# ProPrj_51boardtest_2024-12-12.net
KiCad netlist of a schematic drawn in EasyEDA Pro
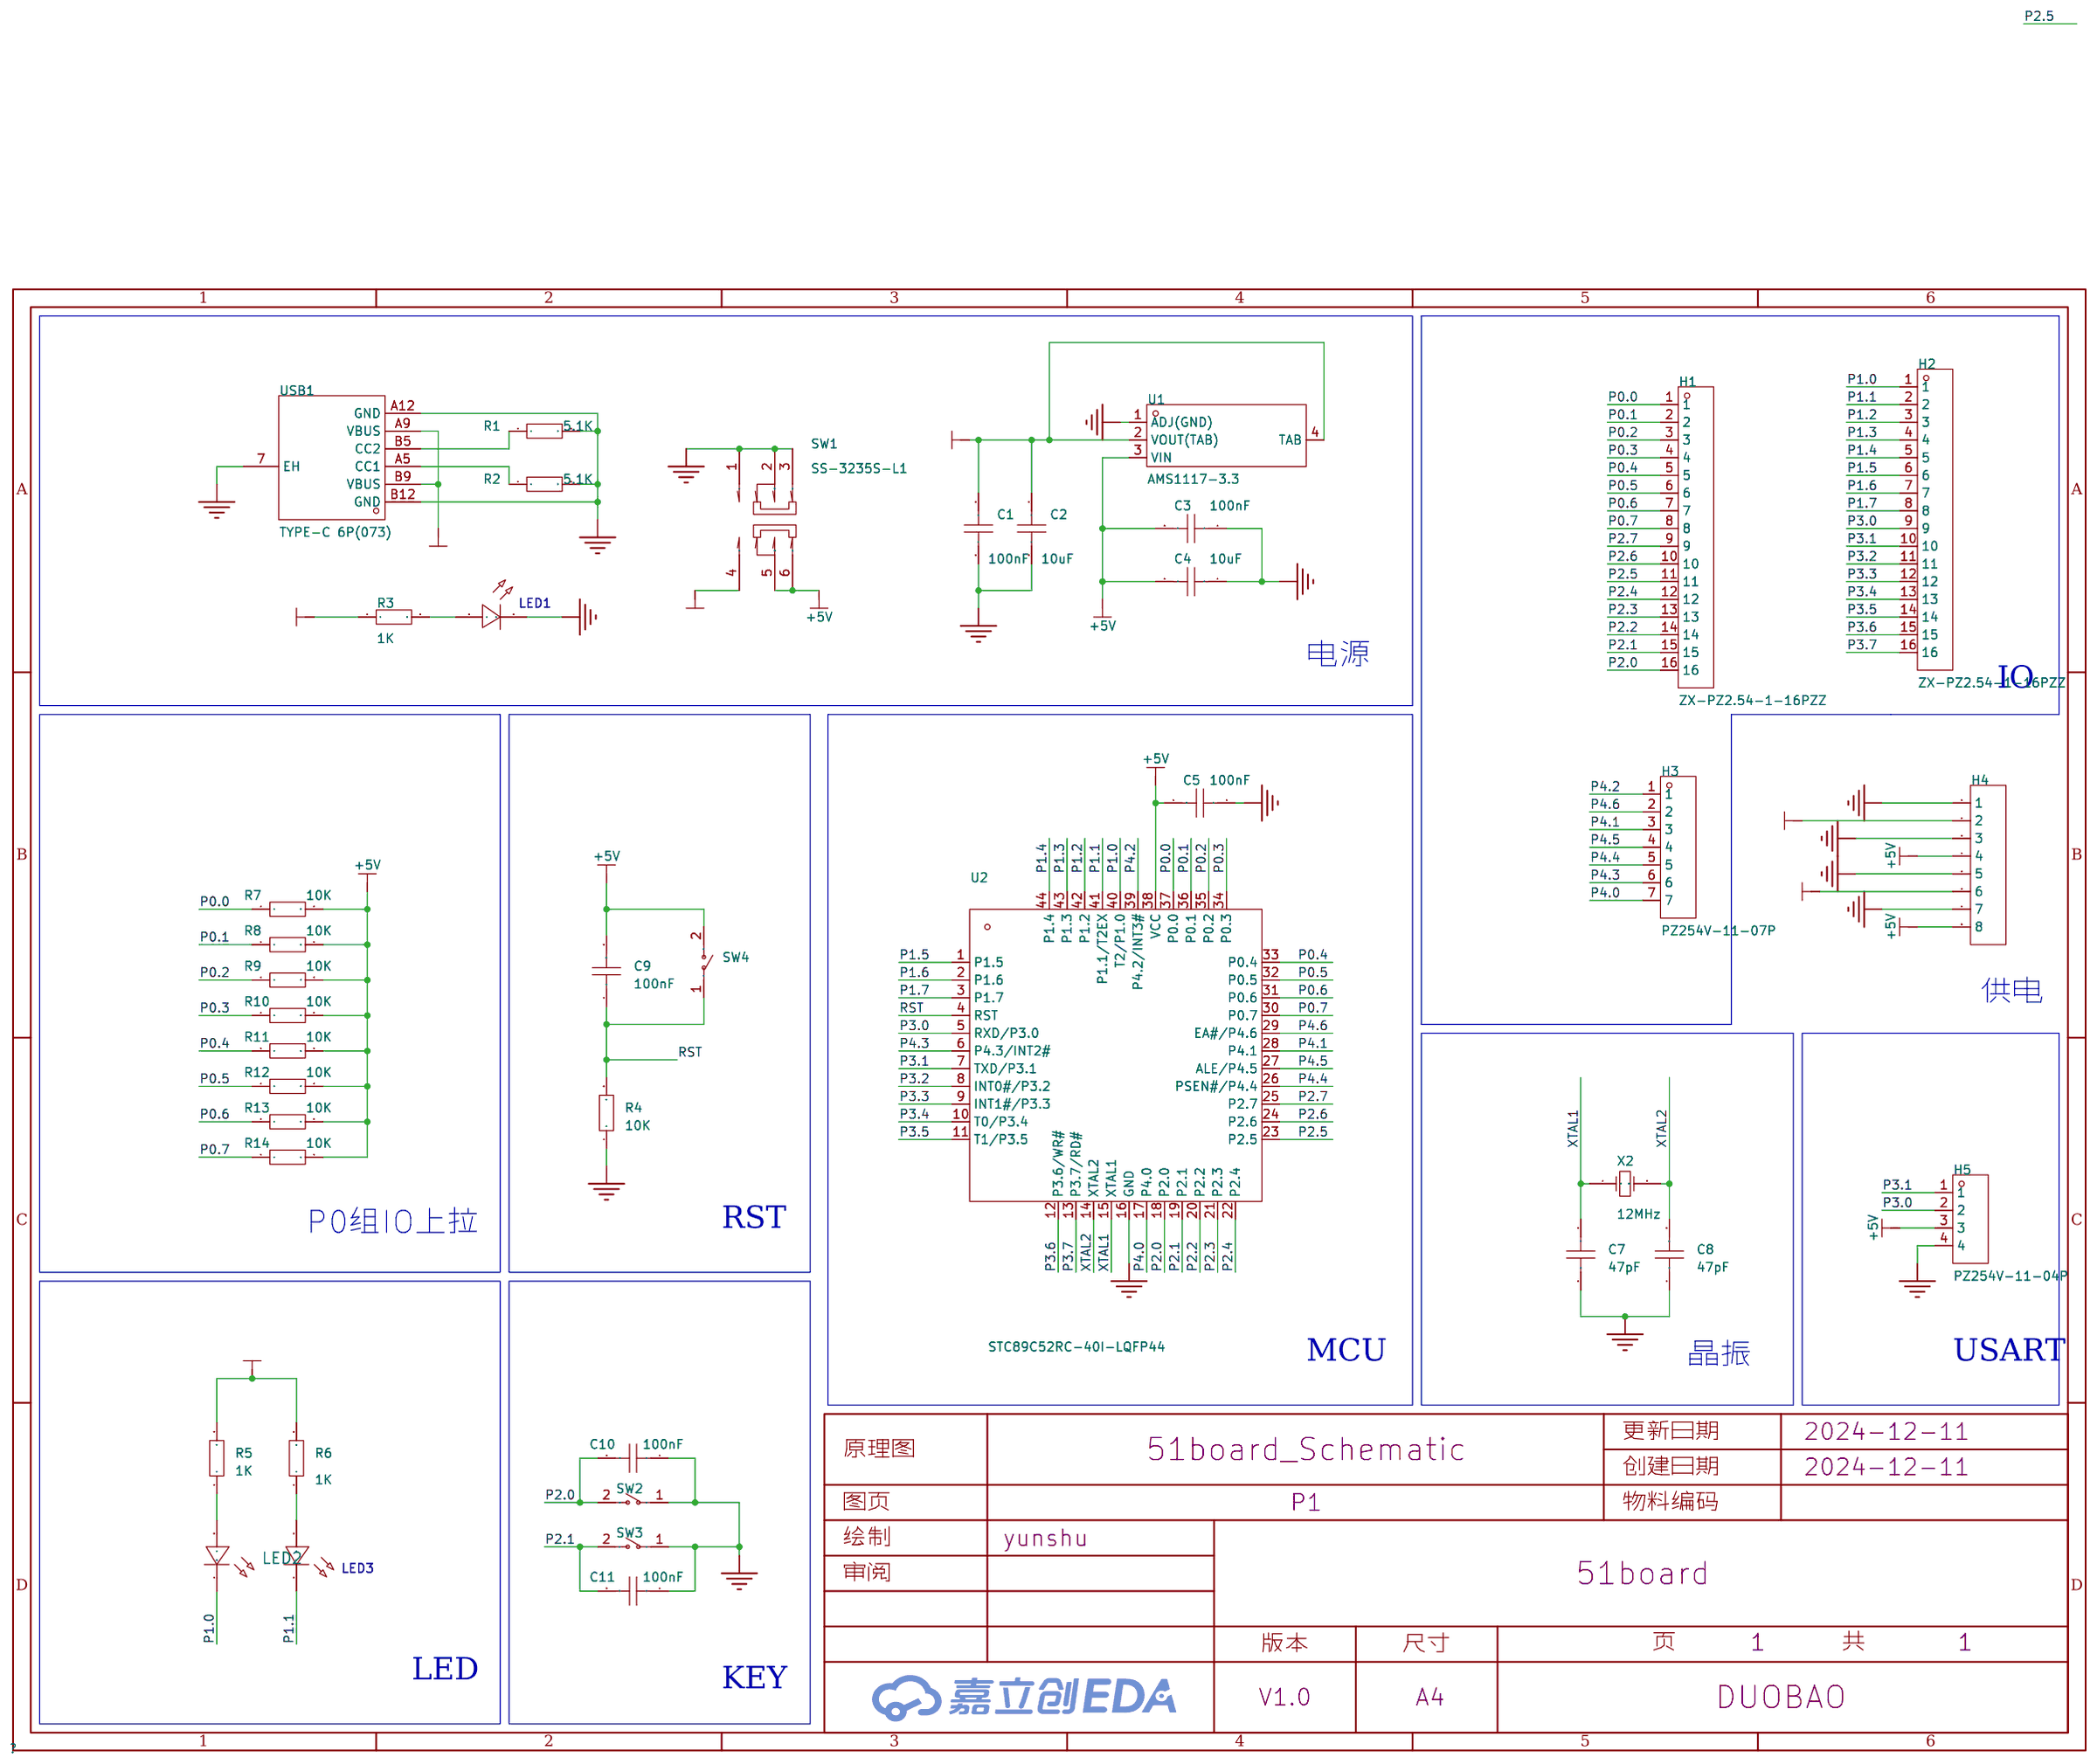
[diagram p0: schematic sheet]

(export (version "E")
  (design (tool "Eeschema 10.0.6"))
  (components
    (comp (ref "C1")
      (value "100nF")
      (footprint "easyedapro:C0805")
      (libsource (lib "easyedapro") (part "CapAcitance"))
    )
    (comp (ref "C2")
      (value "10uF")
      (footprint "easyedapro:C0805")
      (libsource (lib "easyedapro") (part "CapAcitance"))
    )
    (comp (ref "C3")
      (value "100nF")
      (footprint "easyedapro:C0805")
      (libsource (lib "easyedapro") (part "CapAcitance"))
    )
    (comp (ref "C4")
      (value "10uF")
      (footprint "easyedapro:C0805")
      (libsource (lib "easyedapro") (part "CapAcitance"))
    )
    (comp (ref "C5")
      (value "100nF")
      (footprint "easyedapro:C0805")
      (libsource (lib "easyedapro") (part "CapAcitance"))
    )
    (comp (ref "C7")
      (value "47pF")
      (footprint "easyedapro:C0805")
      (libsource (lib "easyedapro") (part "CapAcitance"))
    )
    (comp (ref "C8")
      (value "47pF")
      (footprint "easyedapro:C0805")
      (libsource (lib "easyedapro") (part "CapAcitance"))
    )
    (comp (ref "C9")
      (value "100nF")
      (footprint "easyedapro:C0805")
      (libsource (lib "easyedapro") (part "CapAcitance"))
    )
    (comp (ref "C10")
      (value "100nF")
      (footprint "easyedapro:C0805")
      (libsource (lib "easyedapro") (part "CapAcitance"))
    )
    (comp (ref "C11")
      (value "100nF")
      (footprint "easyedapro:C0805")
      (libsource (lib "easyedapro") (part "CapAcitance"))
    )
    (comp (ref "H1")
      (value "ZX-PZ2.54-1-16PZZ")
      (footprint "easyedapro:HDR-TH_16P-P2.54-V-M")
      (fields (field (name "Manufacturer") "Megastar(兆星)"))
      (libsource (lib "easyedapro") (part "HDR_2.54-1x16P"))
    )
    (comp (ref "H2")
      (value "ZX-PZ2.54-1-16PZZ")
      (footprint "easyedapro:HDR-TH_16P-P2.54-V-M")
      (fields (field (name "Manufacturer") "Megastar(兆星)"))
      (libsource (lib "easyedapro") (part "HDR_2.54-1x16P"))
    )
    (comp (ref "H3")
      (value "PZ254V-11-07P")
      (footprint "easyedapro:HDR-TH_7P-P2.54-V-M")
      (fields (field (name "Manufacturer") "XFCN(兴飞)"))
      (libsource (lib "easyedapro") (part "PZ254V-11-07P"))
    )
    (comp (ref "H4")
      (value "~")
      (footprint "easyedapro:HDR-TH_8P-P2.54-V-F-1")
      (libsource (lib "easyedapro") (part "Header-Female-2.54_1x8"))
    )
    (comp (ref "H5")
      (value "PZ254V-11-04P")
      (footprint "easyedapro:HDR-TH_4P-P2.54-V-M")
      (fields (field (name "Manufacturer") "XFCN(兴飞)"))
      (libsource (lib "easyedapro") (part "PZ254V-11-04P"))
    )
    (comp (ref "LED1")
      (value "~")
      (footprint "easyedapro:LED_0805")
      (libsource (lib "easyedapro") (part "LED_G"))
    )
    (comp (ref "LED2")
      (value "~")
      (footprint "easyedapro:LED_0805")
      (libsource (lib "easyedapro") (part "LED_R"))
    )
    (comp (ref "LED3")
      (value "~")
      (footprint "easyedapro:LED_0805")
      (libsource (lib "easyedapro") (part "LED_B"))
    )
    (comp (ref "R1") (value "5.1K") (footprint "easyedapro:R0805") (libsource (lib "easyedapro") (part "电阻")))
    (comp (ref "R2") (value "5.1K") (footprint "easyedapro:R0805") (libsource (lib "easyedapro") (part "电阻")))
    (comp (ref "R3") (value "1K") (footprint "easyedapro:R0805") (libsource (lib "easyedapro") (part "电阻")))
    (comp (ref "R4") (value "10K") (footprint "easyedapro:R0805") (libsource (lib "easyedapro") (part "电阻")))
    (comp (ref "R5") (value "1K") (footprint "easyedapro:R0805") (libsource (lib "easyedapro") (part "电阻")))
    (comp (ref "R6") (value "1K") (footprint "easyedapro:R0805") (libsource (lib "easyedapro") (part "电阻")))
    (comp (ref "R7") (value "10K") (footprint "easyedapro:R0805") (libsource (lib "easyedapro") (part "电阻")))
    (comp (ref "R8") (value "10K") (footprint "easyedapro:R0805") (libsource (lib "easyedapro") (part "电阻")))
    (comp (ref "R9") (value "10K") (footprint "easyedapro:R0805") (libsource (lib "easyedapro") (part "电阻")))
    (comp (ref "R10") (value "10K") (footprint "easyedapro:R0805") (libsource (lib "easyedapro") (part "电阻")))
    (comp (ref "R11") (value "10K") (footprint "easyedapro:R0805") (libsource (lib "easyedapro") (part "电阻")))
    (comp (ref "R12") (value "10K") (footprint "easyedapro:R0805") (libsource (lib "easyedapro") (part "电阻")))
    (comp (ref "R13") (value "10K") (footprint "easyedapro:R0805") (libsource (lib "easyedapro") (part "电阻")))
    (comp (ref "R14") (value "10K") (footprint "easyedapro:R0805") (libsource (lib "easyedapro") (part "电阻")))
    (comp (ref "SW1")
      (value "SS-3235S-L1")
      (footprint "easyedapro:SW-SMD_SS-3235S-LX")
      (description "电路结构:双刀双掷;安装方式:卧贴;开关颜色:黑色;额定电流(DC):50mA;额定电压(DC):12V;额定电流(AC):50mA;额定电压(AC):12V;机械寿命:1万次;")
      (fields (field (name "Manufacturer") "XKB Connectivity(中国星坤)"))
      (libsource (lib "easyedapro") (part "SS-3235S-L1"))
    )
    (comp (ref "SW2")
      (value "轻触按键 3x6x2.5mm")
      (footprint "easyedapro:SW-SMD_L6.1-W3.7-LS8.0")
      (description "开关长度:6.05mm;开关宽度:3.65mm;开关高度:2.5mm;机械寿命:-;")
      (fields (field (name "Manufacturer") "BBJ"))
      (libsource (lib "easyedapro") (part "轻触按键 3X6X2.5MM"))
    )
    (comp (ref "SW3")
      (value "轻触按键 3x6x2.5mm")
      (footprint "easyedapro:SW-SMD_L6.1-W3.7-LS8.0")
      (description "开关长度:6.05mm;开关宽度:3.65mm;开关高度:2.5mm;机械寿命:-;")
      (fields (field (name "Manufacturer") "BBJ"))
      (libsource (lib "easyedapro") (part "轻触按键 3X6X2.5MM"))
    )
    (comp (ref "SW4")
      (value "轻触按键 3x6x2.5mm")
      (footprint "easyedapro:SW-SMD_L6.1-W3.7-LS8.0")
      (description "开关长度:6.05mm;开关宽度:3.65mm;开关高度:2.5mm;机械寿命:-;")
      (fields (field (name "Manufacturer") "BBJ"))
      (libsource (lib "easyedapro") (part "轻触按键 3X6X2.5MM"))
    )
    (comp (ref "U1")
      (value "AMS1117-3.3")
      (footprint "easyedapro:SOT-223-4_L6.5-W3.5-P2.30-LS7.0-BR")
      (description "输出类型:固定;最大输入电压:18V;输出电压:3.3V;输出电流:1A;电源纹波抑制比(PSRR):60dB@(120Hz);输出极性:正极;")
      (fields (field (name "Manufacturer") "UMW(友台半导体)"))
      (libsource (lib "easyedapro") (part "AMS1117-3.3_C347222"))
    )
    (comp (ref "U2")
      (value "STC89C52RC-40I-LQFP44")
      (footprint "easyedapro:LQFP-44_L10.0-W10.0-P0.80-LS12.0-BL")
      (description "CPU内核:51系列;程序存储容量:8KB;RAM总容量:512Byte;GPIO端口数量:39;工作电压范围:3.3V~5.5V;CPU最大主频:-;程序存储器类型:FLASH;")
      (fields (field (name "Manufacturer") "STC(宏晶)"))
      (libsource (lib "easyedapro") (part "STC89C52RC-40I_C8707"))
    )
    (comp (ref "USB1")
      (value "TYPE-C 6P(073)")
      (footprint "easyedapro:TYPE-C-SMD_TYPE-C-6P_5")
      (description "连接器类型:Type-C;标准:USB 3.1;公母:母;安装方式:卧贴;触点数量:6P;端口数量:1;额定电流 - 电源:3A;工作温度范围:-25°C~+85°C;")
      (fields (field (name "Manufacturer") "SHOU HAN(首韩)"))
      (libsource (lib "easyedapro") (part "TYPE-C 6P(073)"))
    )
    (comp (ref "X2")
      (value "12MHz")
      (footprint "easyedapro:OSC-TH_BD2.0-P0.50")
      (description "晶振类型:直插晶振;频率:12MHz;常温频差:±20ppm;外接负载电容:20pF;频率稳定度(全温):±30ppm;")
      (fields
        (field (name "Manufacturer Part") "TXD12M0002206LDBEO00S")
        (field (name "Manufacturer") "YJX(雅晶鑫)")
      )
      (libsource (lib "easyedapro") (part "TXD12M0002206LDBEO00S"))
    )
  )
  (nets
    (net (code "1") (name "+5V") (class "Default")
      (node (ref "C3") (pin "2") (pinfunction "2_2") (pintype "input"))
      (node (ref "C4") (pin "2") (pinfunction "2_2") (pintype "input"))
      (node (ref "C5") (pin "1") (pinfunction "1_1") (pintype "input"))
      (node (ref "C9") (pin "2") (pinfunction "2_2") (pintype "input"))
      (node (ref "H4") (pin "4") (pinfunction "4_4") (pintype "input"))
      (node (ref "H4") (pin "8") (pinfunction "8_8") (pintype "input"))
      (node (ref "H5") (pin "3") (pinfunction "3_3") (pintype "unspecified"))
      (node (ref "R10") (pin "2") (pinfunction "2_2") (pintype "input"))
      (node (ref "R11") (pin "2") (pinfunction "2_2") (pintype "input"))
      (node (ref "R12") (pin "2") (pinfunction "2_2") (pintype "input"))
      (node (ref "R13") (pin "2") (pinfunction "2_2") (pintype "input"))
      (node (ref "R14") (pin "2") (pinfunction "2_2") (pintype "input"))
      (node (ref "R7") (pin "2") (pinfunction "2_2") (pintype "input"))
      (node (ref "R8") (pin "2") (pinfunction "2_2") (pintype "input"))
      (node (ref "R9") (pin "2") (pinfunction "2_2") (pintype "input"))
      (node (ref "SW1") (pin "5") (pinfunction "5_5") (pintype "unspecified"))
      (node (ref "SW1") (pin "6") (pinfunction "6_6") (pintype "unspecified"))
      (node (ref "SW4") (pin "2") (pinfunction "2_2") (pintype "unspecified"))
      (node (ref "U1") (pin "3") (pinfunction "VIN_3") (pintype "unspecified"))
      (node (ref "U2") (pin "38") (pinfunction "VCC_38") (pintype "unspecified"))
    )
    (net (code "2") (name "/P0.0") (class "Default")
      (node (ref "H1") (pin "1") (pinfunction "1_1") (pintype "input"))
      (node (ref "R7") (pin "1") (pinfunction "1_1") (pintype "input"))
      (node (ref "U2") (pin "37") (pinfunction "P0.0_37") (pintype "unspecified"))
    )
    (net (code "3") (name "/P0.1") (class "Default")
      (node (ref "H1") (pin "2") (pinfunction "2_2") (pintype "input"))
      (node (ref "R8") (pin "1") (pinfunction "1_1") (pintype "input"))
      (node (ref "U2") (pin "36") (pinfunction "P0.1_36") (pintype "unspecified"))
    )
    (net (code "4") (name "/P0.2") (class "Default")
      (node (ref "H1") (pin "3") (pinfunction "3_3") (pintype "input"))
      (node (ref "R9") (pin "1") (pinfunction "1_1") (pintype "input"))
      (node (ref "U2") (pin "35") (pinfunction "P0.2_35") (pintype "unspecified"))
    )
    (net (code "5") (name "/P0.3") (class "Default")
      (node (ref "H1") (pin "4") (pinfunction "4_4") (pintype "input"))
      (node (ref "R10") (pin "1") (pinfunction "1_1") (pintype "input"))
      (node (ref "U2") (pin "34") (pinfunction "P0.3_34") (pintype "unspecified"))
    )
    (net (code "6") (name "/P0.4") (class "Default")
      (node (ref "H1") (pin "5") (pinfunction "5_5") (pintype "input"))
      (node (ref "R11") (pin "1") (pinfunction "1_1") (pintype "input"))
      (node (ref "U2") (pin "33") (pinfunction "P0.4_33") (pintype "unspecified"))
    )
    (net (code "7") (name "/P0.5") (class "Default")
      (node (ref "H1") (pin "6") (pinfunction "6_6") (pintype "input"))
      (node (ref "R12") (pin "1") (pinfunction "1_1") (pintype "input"))
      (node (ref "U2") (pin "32") (pinfunction "P0.5_32") (pintype "unspecified"))
    )
    (net (code "8") (name "/P0.6") (class "Default")
      (node (ref "H1") (pin "7") (pinfunction "7_7") (pintype "input"))
      (node (ref "R13") (pin "1") (pinfunction "1_1") (pintype "input"))
      (node (ref "U2") (pin "31") (pinfunction "P0.6_31") (pintype "unspecified"))
    )
    (net (code "9") (name "/P0.7") (class "Default")
      (node (ref "H1") (pin "8") (pinfunction "8_8") (pintype "input"))
      (node (ref "R14") (pin "1") (pinfunction "1_1") (pintype "input"))
      (node (ref "U2") (pin "30") (pinfunction "P0.7_30") (pintype "unspecified"))
    )
    (net (code "10") (name "/P1.0") (class "Default")
      (node (ref "H2") (pin "1") (pinfunction "1_1") (pintype "input"))
      (node (ref "LED2") (pin "1") (pinfunction "C_1") (pintype "input"))
      (node (ref "U2") (pin "40") (pinfunction "T2/P1.0_40") (pintype "unspecified"))
    )
    (net (code "11") (name "/P1.1") (class "Default")
      (node (ref "H2") (pin "2") (pinfunction "2_2") (pintype "input"))
      (node (ref "LED3") (pin "1") (pinfunction "C_1") (pintype "input"))
      (node (ref "U2") (pin "41") (pinfunction "P1.1/T2EX_41") (pintype "unspecified"))
    )
    (net (code "12") (name "/P1.2") (class "Default")
      (node (ref "H2") (pin "3") (pinfunction "3_3") (pintype "input"))
      (node (ref "U2") (pin "42") (pinfunction "P1.2_42") (pintype "unspecified"))
    )
    (net (code "13") (name "/P1.3") (class "Default")
      (node (ref "H2") (pin "4") (pinfunction "4_4") (pintype "input"))
      (node (ref "U2") (pin "43") (pinfunction "P1.3_43") (pintype "unspecified"))
    )
    (net (code "14") (name "/P1.4") (class "Default")
      (node (ref "H2") (pin "5") (pinfunction "5_5") (pintype "input"))
      (node (ref "U2") (pin "44") (pinfunction "P1.4_44") (pintype "unspecified"))
    )
    (net (code "15") (name "/P1.5") (class "Default")
      (node (ref "H2") (pin "6") (pinfunction "6_6") (pintype "input"))
      (node (ref "U2") (pin "1") (pinfunction "P1.5_1") (pintype "unspecified"))
    )
    (net (code "16") (name "/P1.6") (class "Default")
      (node (ref "H2") (pin "7") (pinfunction "7_7") (pintype "input"))
      (node (ref "U2") (pin "2") (pinfunction "P1.6_2") (pintype "unspecified"))
    )
    (net (code "17") (name "/P1.7") (class "Default")
      (node (ref "H2") (pin "8") (pinfunction "8_8") (pintype "input"))
      (node (ref "U2") (pin "3") (pinfunction "P1.7_3") (pintype "unspecified"))
    )
    (net (code "18") (name "/P2.0") (class "Default")
      (node (ref "C10") (pin "2") (pinfunction "2_2") (pintype "input"))
      (node (ref "H1") (pin "16") (pinfunction "16_16") (pintype "input"))
      (node (ref "SW2") (pin "2") (pinfunction "2_2") (pintype "unspecified"))
      (node (ref "U2") (pin "18") (pinfunction "P2.0_18") (pintype "unspecified"))
    )
    (net (code "19") (name "/P2.1") (class "Default")
      (node (ref "C11") (pin "2") (pinfunction "2_2") (pintype "input"))
      (node (ref "H1") (pin "15") (pinfunction "15_15") (pintype "input"))
      (node (ref "SW3") (pin "2") (pinfunction "2_2") (pintype "unspecified"))
      (node (ref "U2") (pin "19") (pinfunction "P2.1_19") (pintype "unspecified"))
    )
    (net (code "20") (name "/P2.2") (class "Default")
      (node (ref "H1") (pin "14") (pinfunction "14_14") (pintype "input"))
      (node (ref "U2") (pin "20") (pinfunction "P2.2_20") (pintype "unspecified"))
    )
    (net (code "21") (name "/P2.3") (class "Default")
      (node (ref "H1") (pin "13") (pinfunction "13_13") (pintype "input"))
      (node (ref "U2") (pin "21") (pinfunction "P2.3_21") (pintype "unspecified"))
    )
    (net (code "22") (name "/P2.4") (class "Default")
      (node (ref "H1") (pin "12") (pinfunction "12_12") (pintype "input"))
      (node (ref "U2") (pin "22") (pinfunction "P2.4_22") (pintype "unspecified"))
    )
    (net (code "23") (name "/P2.5") (class "Default")
      (node (ref "H1") (pin "11") (pinfunction "11_11") (pintype "input"))
      (node (ref "U2") (pin "23") (pinfunction "P2.5_23") (pintype "unspecified"))
    )
    (net (code "24") (name "/P2.6") (class "Default")
      (node (ref "H1") (pin "10") (pinfunction "10_10") (pintype "input"))
      (node (ref "U2") (pin "24") (pinfunction "P2.6_24") (pintype "unspecified"))
    )
    (net (code "25") (name "/P2.7") (class "Default")
      (node (ref "H1") (pin "9") (pinfunction "9_9") (pintype "input"))
      (node (ref "U2") (pin "25") (pinfunction "P2.7_25") (pintype "unspecified"))
    )
    (net (code "26") (name "/P3.0") (class "Default")
      (node (ref "H2") (pin "9") (pinfunction "9_9") (pintype "input"))
      (node (ref "H5") (pin "2") (pinfunction "2_2") (pintype "unspecified"))
      (node (ref "U2") (pin "5") (pinfunction "RXD/P3.0_5") (pintype "unspecified"))
    )
    (net (code "27") (name "/P3.1") (class "Default")
      (node (ref "H2") (pin "10") (pinfunction "10_10") (pintype "input"))
      (node (ref "H5") (pin "1") (pinfunction "1_1") (pintype "unspecified"))
      (node (ref "U2") (pin "7") (pinfunction "TXD/P3.1_7") (pintype "unspecified"))
    )
    (net (code "28") (name "/P3.2") (class "Default")
      (node (ref "H2") (pin "11") (pinfunction "11_11") (pintype "input"))
      (node (ref "U2") (pin "8") (pinfunction "INT0#/P3.2_8") (pintype "unspecified"))
    )
    (net (code "29") (name "/P3.3") (class "Default")
      (node (ref "H2") (pin "12") (pinfunction "12_12") (pintype "input"))
      (node (ref "U2") (pin "9") (pinfunction "INT1#/P3.3_9") (pintype "unspecified"))
    )
    (net (code "30") (name "/P3.4") (class "Default")
      (node (ref "H2") (pin "13") (pinfunction "13_13") (pintype "input"))
      (node (ref "U2") (pin "10") (pinfunction "T0/P3.4_10") (pintype "unspecified"))
    )
    (net (code "31") (name "/P3.5") (class "Default")
      (node (ref "H2") (pin "14") (pinfunction "14_14") (pintype "input"))
      (node (ref "U2") (pin "11") (pinfunction "T1/P3.5_11") (pintype "unspecified"))
    )
    (net (code "32") (name "/P3.6") (class "Default")
      (node (ref "H2") (pin "15") (pinfunction "15_15") (pintype "input"))
      (node (ref "U2") (pin "12") (pinfunction "P3.6/WR#_12") (pintype "unspecified"))
    )
    (net (code "33") (name "/P3.7") (class "Default")
      (node (ref "H2") (pin "16") (pinfunction "16_16") (pintype "input"))
      (node (ref "U2") (pin "13") (pinfunction "P3.7/RD#_13") (pintype "unspecified"))
    )
    (net (code "34") (name "/P4.0") (class "Default")
      (node (ref "H3") (pin "7") (pinfunction "7_7") (pintype "unspecified"))
      (node (ref "U2") (pin "17") (pinfunction "P4.0_17") (pintype "unspecified"))
    )
    (net (code "35") (name "/P4.1") (class "Default")
      (node (ref "H3") (pin "3") (pinfunction "3_3") (pintype "unspecified"))
      (node (ref "U2") (pin "28") (pinfunction "P4.1_28") (pintype "unspecified"))
    )
    (net (code "36") (name "/P4.2") (class "Default")
      (node (ref "H3") (pin "1") (pinfunction "1_1") (pintype "unspecified"))
      (node (ref "U2") (pin "39") (pinfunction "P4.2/INT3#_39") (pintype "unspecified"))
    )
    (net (code "37") (name "/P4.3") (class "Default")
      (node (ref "H3") (pin "6") (pinfunction "6_6") (pintype "unspecified"))
      (node (ref "U2") (pin "6") (pinfunction "P4.3/INT2#_6") (pintype "unspecified"))
    )
    (net (code "38") (name "/P4.4") (class "Default")
      (node (ref "H3") (pin "5") (pinfunction "5_5") (pintype "unspecified"))
      (node (ref "U2") (pin "26") (pinfunction "PSEN#/P4.4_26") (pintype "unspecified"))
    )
    (net (code "39") (name "/P4.5") (class "Default")
      (node (ref "H3") (pin "4") (pinfunction "4_4") (pintype "unspecified"))
      (node (ref "U2") (pin "27") (pinfunction "ALE/P4.5_27") (pintype "unspecified"))
    )
    (net (code "40") (name "/P4.6") (class "Default")
      (node (ref "H3") (pin "2") (pinfunction "2_2") (pintype "unspecified"))
      (node (ref "U2") (pin "29") (pinfunction "EA#/P4.6_29") (pintype "unspecified"))
    )
    (net (code "41") (name "/RST") (class "Default")
      (node (ref "C9") (pin "1") (pinfunction "1_1") (pintype "input"))
      (node (ref "R4") (pin "2") (pinfunction "2_2") (pintype "input"))
      (node (ref "SW4") (pin "1") (pinfunction "1_1") (pintype "unspecified"))
      (node (ref "U2") (pin "4") (pinfunction "RST_4") (pintype "unspecified"))
    )
    (net (code "42") (name "/XTAL1") (class "Default")
      (node (ref "C7") (pin "2") (pinfunction "2_2") (pintype "input"))
      (node (ref "U2") (pin "15") (pinfunction "XTAL1_15") (pintype "unspecified"))
      (node (ref "X2") (pin "1") (pinfunction "OSC1_1") (pintype "unspecified"))
    )
    (net (code "43") (name "/XTAL2") (class "Default")
      (node (ref "C8") (pin "2") (pinfunction "2_2") (pintype "input"))
      (node (ref "U2") (pin "14") (pinfunction "XTAL2_14") (pintype "unspecified"))
      (node (ref "X2") (pin "2") (pinfunction "OSC2_2") (pintype "unspecified"))
    )
    (net (code "44") (name "GND") (class "Default")
      (node (ref "C1") (pin "2") (pinfunction "2_2") (pintype "input"))
      (node (ref "C10") (pin "1") (pinfunction "1_1") (pintype "input"))
      (node (ref "C11") (pin "1") (pinfunction "1_1") (pintype "input"))
      (node (ref "C2") (pin "2") (pinfunction "2_2") (pintype "input"))
      (node (ref "C3") (pin "1") (pinfunction "1_1") (pintype "input"))
      (node (ref "C4") (pin "1") (pinfunction "1_1") (pintype "input"))
      (node (ref "C5") (pin "2") (pinfunction "2_2") (pintype "input"))
      (node (ref "C7") (pin "1") (pinfunction "1_1") (pintype "input"))
      (node (ref "C8") (pin "1") (pinfunction "1_1") (pintype "input"))
      (node (ref "H4") (pin "1") (pinfunction "1_1") (pintype "input"))
      (node (ref "H4") (pin "3") (pinfunction "3_3") (pintype "input"))
      (node (ref "H4") (pin "5") (pinfunction "5_5") (pintype "input"))
      (node (ref "H4") (pin "7") (pinfunction "7_7") (pintype "input"))
      (node (ref "H5") (pin "4") (pinfunction "4_4") (pintype "unspecified"))
      (node (ref "LED1") (pin "1") (pinfunction "C_1") (pintype "input"))
      (node (ref "R1") (pin "2") (pinfunction "2_2") (pintype "input"))
      (node (ref "R2") (pin "2") (pinfunction "2_2") (pintype "input"))
      (node (ref "R4") (pin "1") (pinfunction "1_1") (pintype "input"))
      (node (ref "SW1") (pin "1") (pinfunction "1_1") (pintype "unspecified"))
      (node (ref "SW1") (pin "2") (pinfunction "2_2") (pintype "unspecified"))
      (node (ref "SW1") (pin "3") (pinfunction "3_3") (pintype "unspecified"))
      (node (ref "SW2") (pin "1") (pinfunction "1_1") (pintype "unspecified"))
      (node (ref "SW3") (pin "1") (pinfunction "1_1") (pintype "unspecified"))
      (node (ref "U1") (pin "1") (pinfunction "ADJ(GND)_1") (pintype "unspecified"))
      (node (ref "U2") (pin "16") (pinfunction "GND_16") (pintype "unspecified"))
      (node (ref "USB1") (pin "7") (pinfunction "EH_7") (pintype "unspecified"))
      (node (ref "USB1") (pin "A12") (pinfunction "GND_A12") (pintype "unspecified"))
      (node (ref "USB1") (pin "B12") (pinfunction "GND_B12") (pintype "unspecified"))
    )
    (net (code "45") (name "Net-(LED1-A)") (class "Default")
      (node (ref "LED1") (pin "2") (pinfunction "A_2") (pintype "input"))
      (node (ref "R3") (pin "2") (pinfunction "2_2") (pintype "input"))
    )
    (net (code "46") (name "Net-(LED2-A)") (class "Default")
      (node (ref "LED2") (pin "2") (pinfunction "A_2") (pintype "input"))
      (node (ref "R5") (pin "1") (pinfunction "1_1") (pintype "input"))
    )
    (net (code "47") (name "Net-(LED3-A)") (class "Default")
      (node (ref "LED3") (pin "2") (pinfunction "A_2") (pintype "input"))
      (node (ref "R6") (pin "1") (pinfunction "1_1") (pintype "input"))
    )
    (net (code "48") (name "Net-(USB1-CC1)") (class "Default")
      (node (ref "R2") (pin "1") (pinfunction "1_1") (pintype "input"))
      (node (ref "USB1") (pin "A5") (pinfunction "CC1_A5") (pintype "unspecified"))
    )
    (net (code "49") (name "Net-(USB1-CC2)") (class "Default")
      (node (ref "R1") (pin "1") (pinfunction "1_1") (pintype "input"))
      (node (ref "USB1") (pin "B5") (pinfunction "CC2_B5") (pintype "unspecified"))
    )
    (net (code "50") (name "VCC+3.3V") (class "Default")
      (node (ref "C1") (pin "1") (pinfunction "1_1") (pintype "input"))
      (node (ref "C2") (pin "1") (pinfunction "1_1") (pintype "input"))
      (node (ref "H4") (pin "2") (pinfunction "2_2") (pintype "input"))
      (node (ref "H4") (pin "6") (pinfunction "6_6") (pintype "input"))
      (node (ref "R3") (pin "1") (pinfunction "1_1") (pintype "input"))
      (node (ref "R5") (pin "2") (pinfunction "2_2") (pintype "input"))
      (node (ref "R6") (pin "2") (pinfunction "2_2") (pintype "input"))
      (node (ref "U1") (pin "2") (pinfunction "VOUT(TAB)_2") (pintype "unspecified"))
      (node (ref "U1") (pin "4") (pinfunction "TAB_4") (pintype "unspecified"))
    )
    (net (code "51") (name "VCC+5V") (class "Default")
      (node (ref "SW1") (pin "4") (pinfunction "4_4") (pintype "unspecified"))
      (node (ref "USB1") (pin "A9") (pinfunction "VBUS_A9") (pintype "unspecified"))
      (node (ref "USB1") (pin "B9") (pinfunction "VBUS_B9") (pintype "unspecified"))
    )
  )
)
